# QDRII_mem.net
KiCad netlist of a schematic drawn in Altium Designer
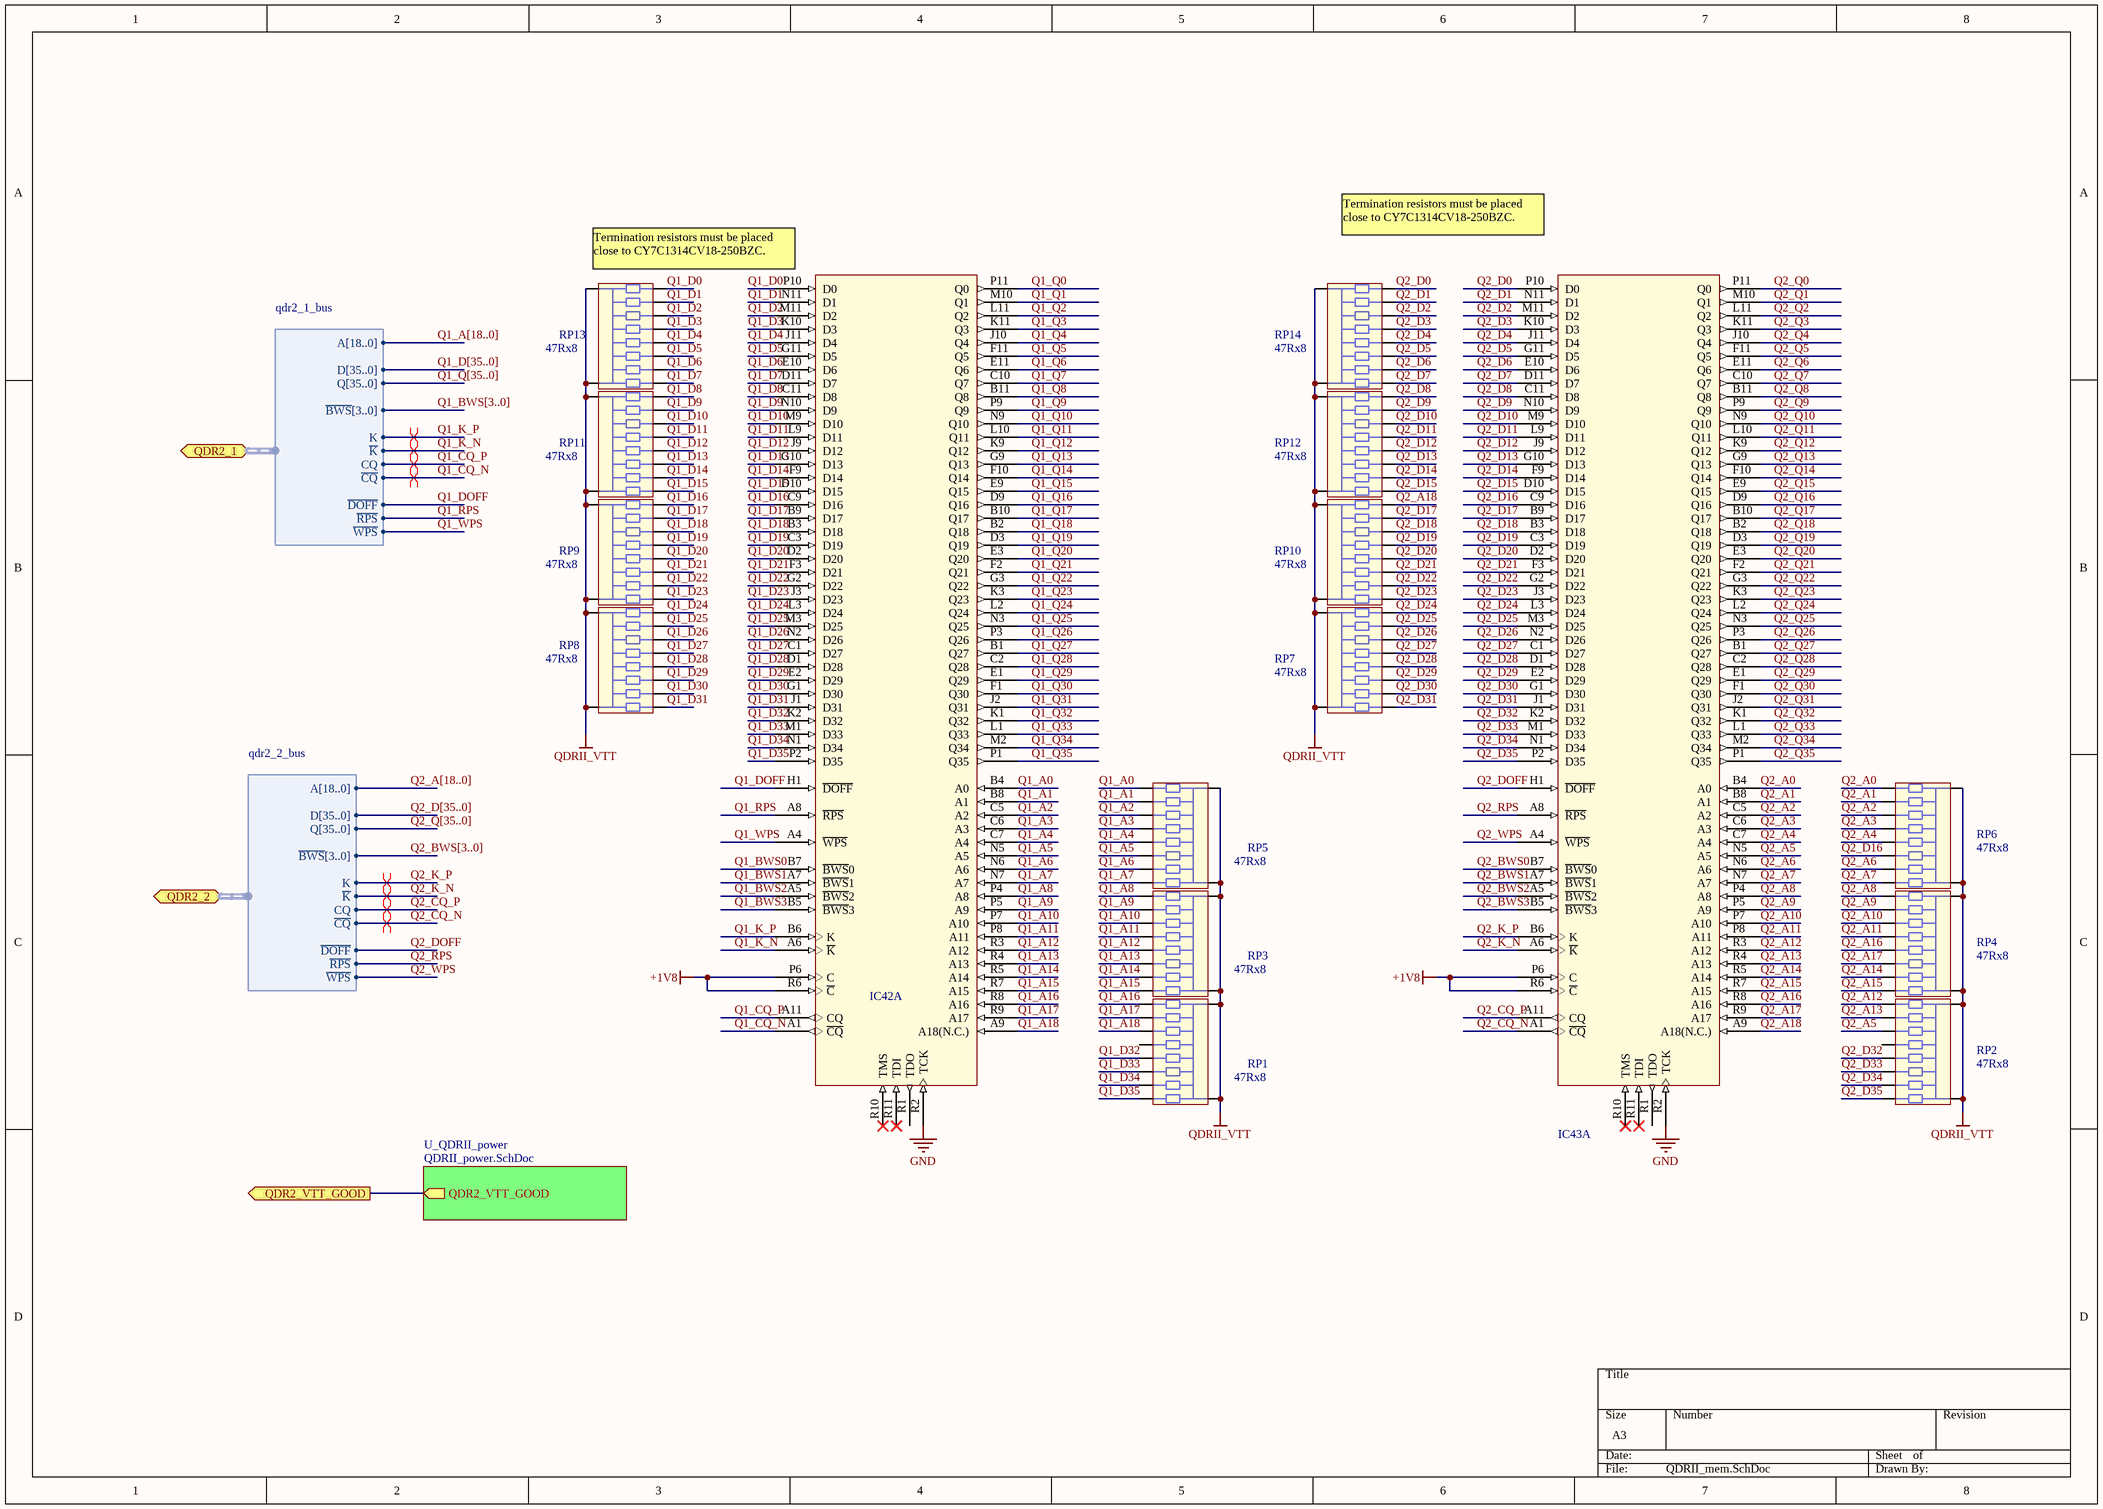
[diagram p0: QDRII_mem.SchDoc]

(export (version "E")
  (design (tool "Eeschema 10.0.6"))
  (components
    (comp (ref "IC42")
      (value "CY7C1314CV18-250BZC")
      (footprint "BGA165C100P11X15_1300X1500X140")
      (description "18-Mbit (512Kx36) QDRII SRAM 2-Word Burst Architecture")
      (libsource (lib "wr_switch") (part "CY7C1314CV18"))
    )
    (comp (ref "IC43")
      (value "CY7C1314CV18-250BZC")
      (footprint "BGA165C100P11X15_1300X1500X140")
      (description "18-Mbit (512Kx36) QDRII SRAM 2-Word Burst Architecture")
      (libsource (lib "wr_switch") (part "CY7C1314CV18"))
    )
    (comp (ref "RP1")
      (value "47Rx8")
      (footprint "EXBE")
      (description "47R, 62.5mW Chip Resistor Bussed Network")
      (fields (field (name "TOLERANCE") "±5%") (field (name "Comment") "47R x 8"))
      (libsource (lib "") (part "EXB-E10C470J_2"))
    )
    (comp (ref "RP2")
      (value "47Rx8")
      (footprint "EXBE")
      (description "47R, 62.5mW Chip Resistor Bussed Network")
      (fields (field (name "TOLERANCE") "±5%") (field (name "Comment") "47R x 8"))
      (libsource (lib "") (part "EXB-E10C470J_5"))
    )
    (comp (ref "RP3")
      (value "47Rx8")
      (footprint "EXBE")
      (description "47R, 62.5mW Chip Resistor Bussed Network")
      (fields (field (name "TOLERANCE") "±5%") (field (name "Comment") "47R x 8"))
      (libsource (lib "") (part "EXB-E10C470J_2"))
    )
    (comp (ref "RP4")
      (value "47Rx8")
      (footprint "EXBE")
      (description "47R, 62.5mW Chip Resistor Bussed Network")
      (fields (field (name "TOLERANCE") "±5%") (field (name "Comment") "47R x 8"))
      (libsource (lib "") (part "EXB-E10C470J_4"))
    )
    (comp (ref "RP5")
      (value "47Rx8")
      (footprint "EXBE")
      (description "47R, 62.5mW Chip Resistor Bussed Network")
      (fields (field (name "TOLERANCE") "±5%") (field (name "Comment") "47R x 8"))
      (libsource (lib "") (part "EXB-E10C470J_2"))
    )
    (comp (ref "RP6")
      (value "47Rx8")
      (footprint "EXBE")
      (description "47R, 62.5mW Chip Resistor Bussed Network")
      (fields (field (name "TOLERANCE") "±5%") (field (name "Comment") "47R x 8"))
      (libsource (lib "") (part "EXB-E10C470J_1"))
    )
    (comp (ref "RP7")
      (value "47Rx8")
      (footprint "EXBE")
      (description "47R, 62.5mW Chip Resistor Bussed Network")
      (fields (field (name "TOLERANCE") "±5%") (field (name "Comment") "47R x 8"))
      (libsource (lib "") (part "EXB-E10C470J_3"))
    )
    (comp (ref "RP8")
      (value "47Rx8")
      (footprint "EXBE")
      (description "47R, 62.5mW Chip Resistor Bussed Network")
      (fields (field (name "TOLERANCE") "±5%") (field (name "Comment") "47R x 8"))
      (libsource (lib "wr_switch") (part "EXB-E10C470J"))
    )
    (comp (ref "RP9")
      (value "47Rx8")
      (footprint "EXBE")
      (description "47R, 62.5mW Chip Resistor Bussed Network")
      (fields (field (name "TOLERANCE") "±5%") (field (name "Comment") "47R x 8"))
      (libsource (lib "wr_switch") (part "EXB-E10C470J"))
    )
    (comp (ref "RP10")
      (value "47Rx8")
      (footprint "EXBE")
      (description "47R, 62.5mW Chip Resistor Bussed Network")
      (fields (field (name "TOLERANCE") "±5%") (field (name "Comment") "47R x 8"))
      (libsource (lib "") (part "EXB-E10C470J_6"))
    )
    (comp (ref "RP11")
      (value "47Rx8")
      (footprint "EXBE")
      (description "47R, 62.5mW Chip Resistor Bussed Network")
      (fields (field (name "TOLERANCE") "±5%") (field (name "Comment") "47R x 8"))
      (libsource (lib "wr_switch") (part "EXB-E10C470J"))
    )
    (comp (ref "RP12")
      (value "47Rx8")
      (footprint "EXBE")
      (description "47R, 62.5mW Chip Resistor Bussed Network")
      (fields (field (name "TOLERANCE") "±5%") (field (name "Comment") "47R x 8"))
      (libsource (lib "wr_switch") (part "EXB-E10C470J"))
    )
    (comp (ref "RP13")
      (value "47Rx8")
      (footprint "EXBE")
      (description "47R, 62.5mW Chip Resistor Bussed Network")
      (fields (field (name "TOLERANCE") "±5%") (field (name "Comment") "47R x 8"))
      (libsource (lib "wr_switch") (part "EXB-E10C470J"))
    )
    (comp (ref "RP14")
      (value "47Rx8")
      (footprint "EXBE")
      (description "47R, 62.5mW Chip Resistor Bussed Network")
      (fields (field (name "TOLERANCE") "±5%") (field (name "Comment") "47R x 8"))
      (libsource (lib "wr_switch") (part "EXB-E10C470J"))
    )
  )
  (nets
    (net (code "3") (name "+1V8") (class "Default")
      (node (ref "IC42") (pin "P6") (pinfunction "C_P6") (pintype "input"))
      (node (ref "IC42") (pin "R6") (pinfunction "~{C}_R6") (pintype "input"))
      (node (ref "IC43") (pin "P6") (pinfunction "C_P6") (pintype "input"))
      (node (ref "IC43") (pin "R6") (pinfunction "~{C}_R6") (pintype "input"))
    )
    (net (code "4") (name "/Q1_A0") (class "Default")
      (node (ref "IC42") (pin "B4") (pinfunction "A0_B4") (pintype "input"))
      (node (ref "RP5") (pin "2") (pinfunction "2_2") (pintype "passive"))
    )
    (net (code "5") (name "/Q1_A1") (class "Default")
      (node (ref "IC42") (pin "B8") (pinfunction "A1_B8") (pintype "input"))
      (node (ref "RP5") (pin "3") (pinfunction "3_3") (pintype "passive"))
    )
    (net (code "6") (name "/Q1_A2") (class "Default")
      (node (ref "IC42") (pin "C5") (pinfunction "A2_C5") (pintype "input"))
      (node (ref "RP5") (pin "4") (pinfunction "4_4") (pintype "passive"))
    )
    (net (code "7") (name "/Q1_A3") (class "Default")
      (node (ref "IC42") (pin "C6") (pinfunction "A3_C6") (pintype "input"))
      (node (ref "RP5") (pin "5") (pinfunction "5_5") (pintype "passive"))
    )
    (net (code "8") (name "/Q1_A4") (class "Default")
      (node (ref "IC42") (pin "C7") (pinfunction "A4_C7") (pintype "input"))
      (node (ref "RP5") (pin "7") (pinfunction "7_7") (pintype "passive"))
    )
    (net (code "9") (name "/Q1_A5") (class "Default")
      (node (ref "IC42") (pin "N5") (pinfunction "A5_N5") (pintype "input"))
      (node (ref "RP5") (pin "8") (pinfunction "8_8") (pintype "passive"))
    )
    (net (code "10") (name "/Q1_A6") (class "Default")
      (node (ref "IC42") (pin "N6") (pinfunction "A6_N6") (pintype "input"))
      (node (ref "RP5") (pin "9") (pinfunction "9_9") (pintype "passive"))
    )
    (net (code "11") (name "/Q1_A7") (class "Default")
      (node (ref "IC42") (pin "N7") (pinfunction "A7_N7") (pintype "input"))
      (node (ref "RP5") (pin "10") (pinfunction "10_10") (pintype "passive"))
    )
    (net (code "12") (name "/Q1_A8") (class "Default")
      (node (ref "IC42") (pin "P4") (pinfunction "A8_P4") (pintype "input"))
      (node (ref "RP3") (pin "2") (pinfunction "2_2") (pintype "passive"))
    )
    (net (code "13") (name "/Q1_A9") (class "Default")
      (node (ref "IC42") (pin "P5") (pinfunction "A9_P5") (pintype "input"))
      (node (ref "RP3") (pin "3") (pinfunction "3_3") (pintype "passive"))
    )
    (net (code "14") (name "/Q1_A10") (class "Default")
      (node (ref "IC42") (pin "P7") (pinfunction "A10_P7") (pintype "input"))
      (node (ref "RP3") (pin "4") (pinfunction "4_4") (pintype "passive"))
    )
    (net (code "15") (name "/Q1_A11") (class "Default")
      (node (ref "IC42") (pin "P8") (pinfunction "A11_P8") (pintype "input"))
      (node (ref "RP3") (pin "5") (pinfunction "5_5") (pintype "passive"))
    )
    (net (code "16") (name "/Q1_A12") (class "Default")
      (node (ref "IC42") (pin "R3") (pinfunction "A12_R3") (pintype "input"))
      (node (ref "RP3") (pin "7") (pinfunction "7_7") (pintype "passive"))
    )
    (net (code "17") (name "/Q1_A13") (class "Default")
      (node (ref "IC42") (pin "R4") (pinfunction "A13_R4") (pintype "input"))
      (node (ref "RP3") (pin "8") (pinfunction "8_8") (pintype "passive"))
    )
    (net (code "18") (name "/Q1_A14") (class "Default")
      (node (ref "IC42") (pin "R5") (pinfunction "A14_R5") (pintype "input"))
      (node (ref "RP3") (pin "9") (pinfunction "9_9") (pintype "passive"))
    )
    (net (code "19") (name "/Q1_A15") (class "Default")
      (node (ref "IC42") (pin "R7") (pinfunction "A15_R7") (pintype "input"))
      (node (ref "RP3") (pin "10") (pinfunction "10_10") (pintype "passive"))
    )
    (net (code "20") (name "/Q1_A16") (class "Default")
      (node (ref "IC42") (pin "R8") (pinfunction "A16_R8") (pintype "input"))
      (node (ref "RP1") (pin "2") (pinfunction "2_2") (pintype "passive"))
    )
    (net (code "21") (name "/Q1_A17") (class "Default")
      (node (ref "IC42") (pin "R9") (pinfunction "A17_R9") (pintype "input"))
      (node (ref "RP1") (pin "3") (pinfunction "3_3") (pintype "passive"))
    )
    (net (code "22") (name "/Q1_A18") (class "Default")
      (node (ref "IC42") (pin "A9") (pinfunction "A18(N.C.)_A9") (pintype "input"))
      (node (ref "RP1") (pin "4") (pinfunction "4_4") (pintype "passive"))
    )
    (net (code "23") (name "/Q1_BWS0") (class "Default")
      (node (ref "IC42") (pin "B7") (pinfunction "~{BWS}0_B7") (pintype "input"))
    )
    (net (code "24") (name "/Q1_BWS1") (class "Default")
      (node (ref "IC42") (pin "A7") (pinfunction "~{BWS}1_A7") (pintype "input"))
    )
    (net (code "25") (name "/Q1_BWS2") (class "Default")
      (node (ref "IC42") (pin "A5") (pinfunction "~{BWS}2_A5") (pintype "input"))
    )
    (net (code "26") (name "/Q1_BWS3") (class "Default")
      (node (ref "IC42") (pin "B5") (pinfunction "~{BWS}3_B5") (pintype "input"))
    )
    (net (code "28") (name "/Q1_CQ_N") (class "Default")
      (node (ref "IC42") (pin "A1") (pinfunction "~{CQ}_A1") (pintype "output"))
    )
    (net (code "29") (name "/Q1_CQ_P") (class "Default")
      (node (ref "IC42") (pin "A11") (pinfunction "CQ_A11") (pintype "output"))
    )
    (net (code "30") (name "/Q1_D0") (class "Default")
      (node (ref "IC42") (pin "P10") (pinfunction "D0_P10") (pintype "input"))
      (node (ref "RP13") (pin "10") (pinfunction "10_10") (pintype "passive"))
    )
    (net (code "31") (name "/Q1_D1") (class "Default")
      (node (ref "IC42") (pin "N11") (pinfunction "D1_N11") (pintype "input"))
      (node (ref "RP13") (pin "9") (pinfunction "9_9") (pintype "passive"))
    )
    (net (code "32") (name "/Q1_D2") (class "Default")
      (node (ref "IC42") (pin "M11") (pinfunction "D2_M11") (pintype "input"))
      (node (ref "RP13") (pin "8") (pinfunction "8_8") (pintype "passive"))
    )
    (net (code "33") (name "/Q1_D3") (class "Default")
      (node (ref "IC42") (pin "K10") (pinfunction "D3_K10") (pintype "input"))
      (node (ref "RP13") (pin "7") (pinfunction "7_7") (pintype "passive"))
    )
    (net (code "34") (name "/Q1_D4") (class "Default")
      (node (ref "IC42") (pin "J11") (pinfunction "D4_J11") (pintype "input"))
      (node (ref "RP13") (pin "5") (pinfunction "5_5") (pintype "passive"))
    )
    (net (code "35") (name "/Q1_D5") (class "Default")
      (node (ref "IC42") (pin "G11") (pinfunction "D5_G11") (pintype "input"))
      (node (ref "RP13") (pin "4") (pinfunction "4_4") (pintype "passive"))
    )
    (net (code "36") (name "/Q1_D6") (class "Default")
      (node (ref "IC42") (pin "E10") (pinfunction "D6_E10") (pintype "input"))
      (node (ref "RP13") (pin "3") (pinfunction "3_3") (pintype "passive"))
    )
    (net (code "37") (name "/Q1_D7") (class "Default")
      (node (ref "IC42") (pin "D11") (pinfunction "D7_D11") (pintype "input"))
      (node (ref "RP13") (pin "2") (pinfunction "2_2") (pintype "passive"))
    )
    (net (code "38") (name "/Q1_D8") (class "Default")
      (node (ref "IC42") (pin "C11") (pinfunction "D8_C11") (pintype "input"))
      (node (ref "RP11") (pin "10") (pinfunction "10_10") (pintype "passive"))
    )
    (net (code "39") (name "/Q1_D9") (class "Default")
      (node (ref "IC42") (pin "N10") (pinfunction "D9_N10") (pintype "input"))
      (node (ref "RP11") (pin "9") (pinfunction "9_9") (pintype "passive"))
    )
    (net (code "40") (name "/Q1_D10") (class "Default")
      (node (ref "IC42") (pin "M9") (pinfunction "D10_M9") (pintype "input"))
      (node (ref "RP11") (pin "8") (pinfunction "8_8") (pintype "passive"))
    )
    (net (code "41") (name "/Q1_D11") (class "Default")
      (node (ref "IC42") (pin "L9") (pinfunction "D11_L9") (pintype "input"))
      (node (ref "RP11") (pin "7") (pinfunction "7_7") (pintype "passive"))
    )
    (net (code "42") (name "/Q1_D12") (class "Default")
      (node (ref "IC42") (pin "J9") (pinfunction "D12_J9") (pintype "input"))
      (node (ref "RP11") (pin "5") (pinfunction "5_5") (pintype "passive"))
    )
    (net (code "43") (name "/Q1_D13") (class "Default")
      (node (ref "IC42") (pin "G10") (pinfunction "D13_G10") (pintype "input"))
      (node (ref "RP11") (pin "4") (pinfunction "4_4") (pintype "passive"))
    )
    (net (code "44") (name "/Q1_D14") (class "Default")
      (node (ref "IC42") (pin "F9") (pinfunction "D14_F9") (pintype "input"))
      (node (ref "RP11") (pin "3") (pinfunction "3_3") (pintype "passive"))
    )
    (net (code "45") (name "/Q1_D15") (class "Default")
      (node (ref "IC42") (pin "D10") (pinfunction "D15_D10") (pintype "input"))
      (node (ref "RP11") (pin "2") (pinfunction "2_2") (pintype "passive"))
    )
    (net (code "46") (name "/Q1_D16") (class "Default")
      (node (ref "IC42") (pin "C9") (pinfunction "D16_C9") (pintype "input"))
      (node (ref "RP9") (pin "10") (pinfunction "10_10") (pintype "passive"))
    )
    (net (code "47") (name "/Q1_D17") (class "Default")
      (node (ref "IC42") (pin "B9") (pinfunction "D17_B9") (pintype "input"))
      (node (ref "RP9") (pin "9") (pinfunction "9_9") (pintype "passive"))
    )
    (net (code "48") (name "/Q1_D18") (class "Default")
      (node (ref "IC42") (pin "B3") (pinfunction "D18_B3") (pintype "input"))
      (node (ref "RP9") (pin "8") (pinfunction "8_8") (pintype "passive"))
    )
    (net (code "49") (name "/Q1_D19") (class "Default")
      (node (ref "IC42") (pin "C3") (pinfunction "D19_C3") (pintype "input"))
      (node (ref "RP9") (pin "7") (pinfunction "7_7") (pintype "passive"))
    )
    (net (code "50") (name "/Q1_D20") (class "Default")
      (node (ref "IC42") (pin "D2") (pinfunction "D20_D2") (pintype "input"))
      (node (ref "RP9") (pin "5") (pinfunction "5_5") (pintype "passive"))
    )
    (net (code "51") (name "/Q1_D21") (class "Default")
      (node (ref "IC42") (pin "F3") (pinfunction "D21_F3") (pintype "input"))
      (node (ref "RP9") (pin "4") (pinfunction "4_4") (pintype "passive"))
    )
    (net (code "52") (name "/Q1_D22") (class "Default")
      (node (ref "IC42") (pin "G2") (pinfunction "D22_G2") (pintype "input"))
      (node (ref "RP9") (pin "3") (pinfunction "3_3") (pintype "passive"))
    )
    (net (code "53") (name "/Q1_D23") (class "Default")
      (node (ref "IC42") (pin "J3") (pinfunction "D23_J3") (pintype "input"))
      (node (ref "RP9") (pin "2") (pinfunction "2_2") (pintype "passive"))
    )
    (net (code "54") (name "/Q1_D24") (class "Default")
      (node (ref "IC42") (pin "L3") (pinfunction "D24_L3") (pintype "input"))
      (node (ref "RP8") (pin "10") (pinfunction "10_10") (pintype "passive"))
    )
    (net (code "55") (name "/Q1_D25") (class "Default")
      (node (ref "IC42") (pin "M3") (pinfunction "D25_M3") (pintype "input"))
      (node (ref "RP8") (pin "9") (pinfunction "9_9") (pintype "passive"))
    )
    (net (code "56") (name "/Q1_D26") (class "Default")
      (node (ref "IC42") (pin "N2") (pinfunction "D26_N2") (pintype "input"))
      (node (ref "RP8") (pin "8") (pinfunction "8_8") (pintype "passive"))
    )
    (net (code "57") (name "/Q1_D27") (class "Default")
      (node (ref "IC42") (pin "C1") (pinfunction "D27_C1") (pintype "input"))
      (node (ref "RP8") (pin "7") (pinfunction "7_7") (pintype "passive"))
    )
    (net (code "58") (name "/Q1_D28") (class "Default")
      (node (ref "IC42") (pin "D1") (pinfunction "D28_D1") (pintype "input"))
      (node (ref "RP8") (pin "5") (pinfunction "5_5") (pintype "passive"))
    )
    (net (code "59") (name "/Q1_D29") (class "Default")
      (node (ref "IC42") (pin "E2") (pinfunction "D29_E2") (pintype "input"))
      (node (ref "RP8") (pin "4") (pinfunction "4_4") (pintype "passive"))
    )
    (net (code "60") (name "/Q1_D30") (class "Default")
      (node (ref "IC42") (pin "G1") (pinfunction "D30_G1") (pintype "input"))
      (node (ref "RP8") (pin "3") (pinfunction "3_3") (pintype "passive"))
    )
    (net (code "61") (name "/Q1_D31") (class "Default")
      (node (ref "IC42") (pin "J1") (pinfunction "D31_J1") (pintype "input"))
      (node (ref "RP8") (pin "2") (pinfunction "2_2") (pintype "passive"))
    )
    (net (code "62") (name "/Q1_D32") (class "Default")
      (node (ref "IC42") (pin "K2") (pinfunction "D32_K2") (pintype "input"))
      (node (ref "RP1") (pin "7") (pinfunction "7_7") (pintype "passive"))
    )
    (net (code "63") (name "/Q1_D33") (class "Default")
      (node (ref "IC42") (pin "M1") (pinfunction "D33_M1") (pintype "input"))
      (node (ref "RP1") (pin "8") (pinfunction "8_8") (pintype "passive"))
    )
    (net (code "64") (name "/Q1_D34") (class "Default")
      (node (ref "IC42") (pin "N1") (pinfunction "D34_N1") (pintype "input"))
      (node (ref "RP1") (pin "9") (pinfunction "9_9") (pintype "passive"))
    )
    (net (code "65") (name "/Q1_D35") (class "Default")
      (node (ref "IC42") (pin "P2") (pinfunction "D35_P2") (pintype "input"))
      (node (ref "RP1") (pin "10") (pinfunction "10_10") (pintype "passive"))
    )
    (net (code "66") (name "/Q1_DOFF") (class "Default")
      (node (ref "IC42") (pin "H1") (pinfunction "~{DOFF}_H1") (pintype "input"))
    )
    (net (code "68") (name "/Q1_K_N") (class "Default")
      (node (ref "IC42") (pin "A6") (pinfunction "~{K}_A6") (pintype "input"))
    )
    (net (code "69") (name "/Q1_K_P") (class "Default")
      (node (ref "IC42") (pin "B6") (pinfunction "K_B6") (pintype "input"))
    )
    (net (code "70") (name "/Q1_Q0") (class "Default")
      (node (ref "IC42") (pin "P11") (pinfunction "Q0_P11") (pintype "output"))
    )
    (net (code "71") (name "/Q1_Q1") (class "Default")
      (node (ref "IC42") (pin "M10") (pinfunction "Q1_M10") (pintype "output"))
    )
    (net (code "72") (name "/Q1_Q2") (class "Default")
      (node (ref "IC42") (pin "L11") (pinfunction "Q2_L11") (pintype "output"))
    )
    (net (code "73") (name "/Q1_Q3") (class "Default")
      (node (ref "IC42") (pin "K11") (pinfunction "Q3_K11") (pintype "output"))
    )
    (net (code "74") (name "/Q1_Q4") (class "Default")
      (node (ref "IC42") (pin "J10") (pinfunction "Q4_J10") (pintype "output"))
    )
    (net (code "75") (name "/Q1_Q5") (class "Default")
      (node (ref "IC42") (pin "F11") (pinfunction "Q5_F11") (pintype "output"))
    )
    (net (code "76") (name "/Q1_Q6") (class "Default")
      (node (ref "IC42") (pin "E11") (pinfunction "Q6_E11") (pintype "output"))
    )
    (net (code "77") (name "/Q1_Q7") (class "Default")
      (node (ref "IC42") (pin "C10") (pinfunction "Q7_C10") (pintype "output"))
    )
    (net (code "78") (name "/Q1_Q8") (class "Default")
      (node (ref "IC42") (pin "B11") (pinfunction "Q8_B11") (pintype "output"))
    )
    (net (code "79") (name "/Q1_Q9") (class "Default")
      (node (ref "IC42") (pin "P9") (pinfunction "Q9_P9") (pintype "output"))
    )
    (net (code "80") (name "/Q1_Q10") (class "Default")
      (node (ref "IC42") (pin "N9") (pinfunction "Q10_N9") (pintype "output"))
    )
    (net (code "81") (name "/Q1_Q11") (class "Default")
      (node (ref "IC42") (pin "L10") (pinfunction "Q11_L10") (pintype "output"))
    )
    (net (code "82") (name "/Q1_Q12") (class "Default")
      (node (ref "IC42") (pin "K9") (pinfunction "Q12_K9") (pintype "output"))
    )
    (net (code "83") (name "/Q1_Q13") (class "Default")
      (node (ref "IC42") (pin "G9") (pinfunction "Q13_G9") (pintype "output"))
    )
    (net (code "84") (name "/Q1_Q14") (class "Default")
      (node (ref "IC42") (pin "F10") (pinfunction "Q14_F10") (pintype "output"))
    )
    (net (code "85") (name "/Q1_Q15") (class "Default")
      (node (ref "IC42") (pin "E9") (pinfunction "Q15_E9") (pintype "output"))
    )
    (net (code "86") (name "/Q1_Q16") (class "Default")
      (node (ref "IC42") (pin "D9") (pinfunction "Q16_D9") (pintype "output"))
    )
    (net (code "87") (name "/Q1_Q17") (class "Default")
      (node (ref "IC42") (pin "B10") (pinfunction "Q17_B10") (pintype "output"))
    )
    (net (code "88") (name "/Q1_Q18") (class "Default")
      (node (ref "IC42") (pin "B2") (pinfunction "Q18_B2") (pintype "output"))
    )
    (net (code "89") (name "/Q1_Q19") (class "Default")
      (node (ref "IC42") (pin "D3") (pinfunction "Q19_D3") (pintype "output"))
    )
    (net (code "90") (name "/Q1_Q20") (class "Default")
      (node (ref "IC42") (pin "E3") (pinfunction "Q20_E3") (pintype "output"))
    )
    (net (code "91") (name "/Q1_Q21") (class "Default")
      (node (ref "IC42") (pin "F2") (pinfunction "Q21_F2") (pintype "output"))
    )
    (net (code "92") (name "/Q1_Q22") (class "Default")
      (node (ref "IC42") (pin "G3") (pinfunction "Q22_G3") (pintype "output"))
    )
    (net (code "93") (name "/Q1_Q23") (class "Default")
      (node (ref "IC42") (pin "K3") (pinfunction "Q23_K3") (pintype "output"))
    )
    (net (code "94") (name "/Q1_Q24") (class "Default")
      (node (ref "IC42") (pin "L2") (pinfunction "Q24_L2") (pintype "output"))
    )
    (net (code "95") (name "/Q1_Q25") (class "Default")
      (node (ref "IC42") (pin "N3") (pinfunction "Q25_N3") (pintype "output"))
    )
    (net (code "96") (name "/Q1_Q26") (class "Default")
      (node (ref "IC42") (pin "P3") (pinfunction "Q26_P3") (pintype "output"))
    )
    (net (code "97") (name "/Q1_Q27") (class "Default")
      (node (ref "IC42") (pin "B1") (pinfunction "Q27_B1") (pintype "output"))
    )
    (net (code "98") (name "/Q1_Q28") (class "Default")
      (node (ref "IC42") (pin "C2") (pinfunction "Q28_C2") (pintype "output"))
    )
    (net (code "99") (name "/Q1_Q29") (class "Default")
      (node (ref "IC42") (pin "E1") (pinfunction "Q29_E1") (pintype "output"))
    )
    (net (code "100") (name "/Q1_Q30") (class "Default")
      (node (ref "IC42") (pin "F1") (pinfunction "Q30_F1") (pintype "output"))
    )
    (net (code "101") (name "/Q1_Q31") (class "Default")
      (node (ref "IC42") (pin "J2") (pinfunction "Q31_J2") (pintype "output"))
    )
    (net (code "102") (name "/Q1_Q32") (class "Default")
      (node (ref "IC42") (pin "K1") (pinfunction "Q32_K1") (pintype "output"))
    )
    (net (code "103") (name "/Q1_Q33") (class "Default")
      (node (ref "IC42") (pin "L1") (pinfunction "Q33_L1") (pintype "output"))
    )
    (net (code "104") (name "/Q1_Q34") (class "Default")
      (node (ref "IC42") (pin "M2") (pinfunction "Q34_M2") (pintype "output"))
    )
    (net (code "105") (name "/Q1_Q35") (class "Default")
      (node (ref "IC42") (pin "P1") (pinfunction "Q35_P1") (pintype "output"))
    )
    (net (code "107") (name "/Q1_RPS") (class "Default")
      (node (ref "IC42") (pin "A8") (pinfunction "~{RPS}_A8") (pintype "input"))
    )
    (net (code "108") (name "/Q1_WPS") (class "Default")
      (node (ref "IC42") (pin "A4") (pinfunction "~{WPS}_A4") (pintype "input"))
    )
    (net (code "109") (name "/Q2_A0") (class "Default")
      (node (ref "IC43") (pin "B4") (pinfunction "A0_B4") (pintype "input"))
      (node (ref "RP6") (pin "5") (pinfunction "5_5") (pintype "passive"))
    )
    (net (code "110") (name "/Q2_A1") (class "Default")
      (node (ref "IC43") (pin "B8") (pinfunction "A1_B8") (pintype "input"))
      (node (ref "RP6") (pin "10") (pinfunction "10_10") (pintype "passive"))
    )
    (net (code "111") (name "/Q2_A2") (class "Default")
      (node (ref "IC43") (pin "C5") (pinfunction "A2_C5") (pintype "input"))
      (node (ref "RP6") (pin "7") (pinfunction "7_7") (pintype "passive"))
    )
    (net (code "112") (name "/Q2_A3") (class "Default")
      (node (ref "IC43") (pin "C6") (pinfunction "A3_C6") (pintype "input"))
      (node (ref "RP6") (pin "8") (pinfunction "8_8") (pintype "passive"))
    )
    (net (code "113") (name "/Q2_A4") (class "Default")
      (node (ref "IC43") (pin "C7") (pinfunction "A4_C7") (pintype "input"))
      (node (ref "RP6") (pin "9") (pinfunction "9_9") (pintype "passive"))
    )
    (net (code "114") (name "/Q2_A5") (class "Default")
      (node (ref "IC43") (pin "N5") (pinfunction "A5_N5") (pintype "input"))
      (node (ref "RP2") (pin "9") (pinfunction "9_9") (pintype "passive"))
    )
    (net (code "115") (name "/Q2_A6") (class "Default")
      (node (ref "IC43") (pin "N6") (pinfunction "A6_N6") (pintype "input"))
      (node (ref "RP6") (pin "3") (pinfunction "3_3") (pintype "passive"))
    )
    (net (code "116") (name "/Q2_A7") (class "Default")
      (node (ref "IC43") (pin "N7") (pinfunction "A7_N7") (pintype "input"))
      (node (ref "RP6") (pin "4") (pinfunction "4_4") (pintype "passive"))
    )
    (net (code "117") (name "/Q2_A8") (class "Default")
      (node (ref "IC43") (pin "P4") (pinfunction "A8_P4") (pintype "input"))
      (node (ref "RP4") (pin "10") (pinfunction "10_10") (pintype "passive"))
    )
    (net (code "118") (name "/Q2_A9") (class "Default")
      (node (ref "IC43") (pin "P5") (pinfunction "A9_P5") (pintype "input"))
      (node (ref "RP4") (pin "9") (pinfunction "9_9") (pintype "passive"))
    )
    (net (code "119") (name "/Q2_A10") (class "Default")
      (node (ref "IC43") (pin "P7") (pinfunction "A10_P7") (pintype "input"))
      (node (ref "RP4") (pin "5") (pinfunction "5_5") (pintype "passive"))
    )
    (net (code "120") (name "/Q2_A11") (class "Default")
      (node (ref "IC43") (pin "P8") (pinfunction "A11_P8") (pintype "input"))
      (node (ref "RP4") (pin "3") (pinfunction "3_3") (pintype "passive"))
    )
    (net (code "121") (name "/Q2_A12") (class "Default")
      (node (ref "IC43") (pin "R3") (pinfunction "A12_R3") (pintype "input"))
      (node (ref "RP2") (pin "10") (pinfunction "10_10") (pintype "passive"))
    )
    (net (code "122") (name "/Q2_A13") (class "Default")
      (node (ref "IC43") (pin "R4") (pinfunction "A13_R4") (pintype "input"))
      (node (ref "RP2") (pin "7") (pinfunction "7_7") (pintype "passive"))
    )
    (net (code "123") (name "/Q2_A14") (class "Default")
      (node (ref "IC43") (pin "R5") (pinfunction "A14_R5") (pintype "input"))
      (node (ref "RP4") (pin "8") (pinfunction "8_8") (pintype "passive"))
    )
    (net (code "124") (name "/Q2_A15") (class "Default")
      (node (ref "IC43") (pin "R7") (pinfunction "A15_R7") (pintype "input"))
      (node (ref "RP4") (pin "7") (pinfunction "7_7") (pintype "passive"))
    )
    (net (code "125") (name "/Q2_A16") (class "Default")
      (node (ref "IC43") (pin "R8") (pinfunction "A16_R8") (pintype "input"))
      (node (ref "RP4") (pin "4") (pinfunction "4_4") (pintype "passive"))
    )
    (net (code "126") (name "/Q2_A17") (class "Default")
      (node (ref "IC43") (pin "R9") (pinfunction "A17_R9") (pintype "input"))
      (node (ref "RP4") (pin "2") (pinfunction "2_2") (pintype "passive"))
    )
    (net (code "127") (name "/Q2_A18") (class "Default")
      (node (ref "IC43") (pin "A9") (pinfunction "A18(N.C.)_A9") (pintype "input"))
      (node (ref "RP10") (pin "5") (pinfunction "5_5") (pintype "passive"))
    )
    (net (code "128") (name "/Q2_BWS0") (class "Default")
      (node (ref "IC43") (pin "B7") (pinfunction "~{BWS}0_B7") (pintype "input"))
    )
    (net (code "129") (name "/Q2_BWS1") (class "Default")
      (node (ref "IC43") (pin "A7") (pinfunction "~{BWS}1_A7") (pintype "input"))
    )
    (net (code "130") (name "/Q2_BWS2") (class "Default")
      (node (ref "IC43") (pin "A5") (pinfunction "~{BWS}2_A5") (pintype "input"))
    )
    (net (code "131") (name "/Q2_BWS3") (class "Default")
      (node (ref "IC43") (pin "B5") (pinfunction "~{BWS}3_B5") (pintype "input"))
    )
    (net (code "133") (name "/Q2_CQ_N") (class "Default")
      (node (ref "IC43") (pin "A1") (pinfunction "~{CQ}_A1") (pintype "output"))
    )
    (net (code "134") (name "/Q2_CQ_P") (class "Default")
      (node (ref "IC43") (pin "A11") (pinfunction "CQ_A11") (pintype "output"))
    )
    (net (code "135") (name "/Q2_D0") (class "Default")
      (node (ref "IC43") (pin "P10") (pinfunction "D0_P10") (pintype "input"))
      (node (ref "RP14") (pin "10") (pinfunction "10_10") (pintype "passive"))
    )
    (net (code "136") (name "/Q2_D1") (class "Default")
      (node (ref "IC43") (pin "N11") (pinfunction "D1_N11") (pintype "input"))
      (node (ref "RP14") (pin "9") (pinfunction "9_9") (pintype "passive"))
    )
    (net (code "137") (name "/Q2_D2") (class "Default")
      (node (ref "IC43") (pin "M11") (pinfunction "D2_M11") (pintype "input"))
      (node (ref "RP14") (pin "8") (pinfunction "8_8") (pintype "passive"))
    )
    (net (code "138") (name "/Q2_D3") (class "Default")
      (node (ref "IC43") (pin "K10") (pinfunction "D3_K10") (pintype "input"))
      (node (ref "RP14") (pin "7") (pinfunction "7_7") (pintype "passive"))
    )
    (net (code "139") (name "/Q2_D4") (class "Default")
      (node (ref "IC43") (pin "J11") (pinfunction "D4_J11") (pintype "input"))
      (node (ref "RP14") (pin "5") (pinfunction "5_5") (pintype "passive"))
    )
    (net (code "140") (name "/Q2_D5") (class "Default")
      (node (ref "IC43") (pin "G11") (pinfunction "D5_G11") (pintype "input"))
      (node (ref "RP14") (pin "4") (pinfunction "4_4") (pintype "passive"))
    )
    (net (code "141") (name "/Q2_D6") (class "Default")
      (node (ref "IC43") (pin "E10") (pinfunction "D6_E10") (pintype "input"))
      (node (ref "RP14") (pin "3") (pinfunction "3_3") (pintype "passive"))
    )
    (net (code "142") (name "/Q2_D7") (class "Default")
      (node (ref "IC43") (pin "D11") (pinfunction "D7_D11") (pintype "input"))
      (node (ref "RP14") (pin "2") (pinfunction "2_2") (pintype "passive"))
    )
    (net (code "143") (name "/Q2_D8") (class "Default")
      (node (ref "IC43") (pin "C11") (pinfunction "D8_C11") (pintype "input"))
      (node (ref "RP12") (pin "10") (pinfunction "10_10") (pintype "passive"))
    )
    (net (code "144") (name "/Q2_D9") (class "Default")
      (node (ref "IC43") (pin "N10") (pinfunction "D9_N10") (pintype "input"))
      (node (ref "RP12") (pin "9") (pinfunction "9_9") (pintype "passive"))
    )
    (net (code "145") (name "/Q2_D10") (class "Default")
      (node (ref "IC43") (pin "M9") (pinfunction "D10_M9") (pintype "input"))
      (node (ref "RP12") (pin "8") (pinfunction "8_8") (pintype "passive"))
    )
    (net (code "146") (name "/Q2_D11") (class "Default")
      (node (ref "IC43") (pin "L9") (pinfunction "D11_L9") (pintype "input"))
      (node (ref "RP12") (pin "7") (pinfunction "7_7") (pintype "passive"))
    )
    (net (code "147") (name "/Q2_D12") (class "Default")
      (node (ref "IC43") (pin "J9") (pinfunction "D12_J9") (pintype "input"))
      (node (ref "RP12") (pin "5") (pinfunction "5_5") (pintype "passive"))
    )
    (net (code "148") (name "/Q2_D13") (class "Default")
      (node (ref "IC43") (pin "G10") (pinfunction "D13_G10") (pintype "input"))
      (node (ref "RP12") (pin "4") (pinfunction "4_4") (pintype "passive"))
    )
    (net (code "149") (name "/Q2_D14") (class "Default")
      (node (ref "IC43") (pin "F9") (pinfunction "D14_F9") (pintype "input"))
      (node (ref "RP12") (pin "3") (pinfunction "3_3") (pintype "passive"))
    )
    (net (code "150") (name "/Q2_D15") (class "Default")
      (node (ref "IC43") (pin "D10") (pinfunction "D15_D10") (pintype "input"))
      (node (ref "RP12") (pin "2") (pinfunction "2_2") (pintype "passive"))
    )
    (net (code "151") (name "/Q2_D16") (class "Default")
      (node (ref "IC43") (pin "C9") (pinfunction "D16_C9") (pintype "input"))
      (node (ref "RP6") (pin "2") (pinfunction "2_2") (pintype "passive"))
    )
    (net (code "152") (name "/Q2_D17") (class "Default")
      (node (ref "IC43") (pin "B9") (pinfunction "D17_B9") (pintype "input"))
      (node (ref "RP10") (pin "4") (pinfunction "4_4") (pintype "passive"))
    )
    (net (code "153") (name "/Q2_D18") (class "Default")
      (node (ref "IC43") (pin "B3") (pinfunction "D18_B3") (pintype "input"))
      (node (ref "RP10") (pin "10") (pinfunction "10_10") (pintype "passive"))
    )
    (net (code "154") (name "/Q2_D19") (class "Default")
      (node (ref "IC43") (pin "C3") (pinfunction "D19_C3") (pintype "input"))
      (node (ref "RP10") (pin "9") (pinfunction "9_9") (pintype "passive"))
    )
    (net (code "155") (name "/Q2_D20") (class "Default")
      (node (ref "IC43") (pin "D2") (pinfunction "D20_D2") (pintype "input"))
      (node (ref "RP10") (pin "8") (pinfunction "8_8") (pintype "passive"))
    )
    (net (code "156") (name "/Q2_D21") (class "Default")
      (node (ref "IC43") (pin "F3") (pinfunction "D21_F3") (pintype "input"))
      (node (ref "RP10") (pin "2") (pinfunction "2_2") (pintype "passive"))
    )
    (net (code "157") (name "/Q2_D22") (class "Default")
      (node (ref "IC43") (pin "G2") (pinfunction "D22_G2") (pintype "input"))
      (node (ref "RP10") (pin "7") (pinfunction "7_7") (pintype "passive"))
    )
    (net (code "158") (name "/Q2_D23") (class "Default")
      (node (ref "IC43") (pin "J3") (pinfunction "D23_J3") (pintype "input"))
      (node (ref "RP10") (pin "3") (pinfunction "3_3") (pintype "passive"))
    )
    (net (code "159") (name "/Q2_D24") (class "Default")
      (node (ref "IC43") (pin "L3") (pinfunction "D24_L3") (pintype "input"))
      (node (ref "RP7") (pin "4") (pinfunction "4_4") (pintype "passive"))
    )
    (net (code "160") (name "/Q2_D25") (class "Default")
      (node (ref "IC43") (pin "M3") (pinfunction "D25_M3") (pintype "input"))
      (node (ref "RP7") (pin "3") (pinfunction "3_3") (pintype "passive"))
    )
    (net (code "161") (name "/Q2_D26") (class "Default")
      (node (ref "IC43") (pin "N2") (pinfunction "D26_N2") (pintype "input"))
      (node (ref "RP7") (pin "2") (pinfunction "2_2") (pintype "passive"))
    )
    (net (code "162") (name "/Q2_D27") (class "Default")
      (node (ref "IC43") (pin "C1") (pinfunction "D27_C1") (pintype "input"))
      (node (ref "RP7") (pin "10") (pinfunction "10_10") (pintype "passive"))
    )
    (net (code "163") (name "/Q2_D28") (class "Default")
      (node (ref "IC43") (pin "D1") (pinfunction "D28_D1") (pintype "input"))
      (node (ref "RP7") (pin "9") (pinfunction "9_9") (pintype "passive"))
    )
    (net (code "164") (name "/Q2_D29") (class "Default")
      (node (ref "IC43") (pin "E2") (pinfunction "D29_E2") (pintype "input"))
      (node (ref "RP7") (pin "8") (pinfunction "8_8") (pintype "passive"))
    )
    (net (code "165") (name "/Q2_D30") (class "Default")
      (node (ref "IC43") (pin "G1") (pinfunction "D30_G1") (pintype "input"))
      (node (ref "RP7") (pin "7") (pinfunction "7_7") (pintype "passive"))
    )
    (net (code "166") (name "/Q2_D31") (class "Default")
      (node (ref "IC43") (pin "J1") (pinfunction "D31_J1") (pintype "input"))
      (node (ref "RP7") (pin "5") (pinfunction "5_5") (pintype "passive"))
    )
    (net (code "167") (name "/Q2_D32") (class "Default")
      (node (ref "IC43") (pin "K2") (pinfunction "D32_K2") (pintype "input"))
      (node (ref "RP2") (pin "5") (pinfunction "5_5") (pintype "passive"))
    )
    (net (code "168") (name "/Q2_D33") (class "Default")
      (node (ref "IC43") (pin "M1") (pinfunction "D33_M1") (pintype "input"))
      (node (ref "RP2") (pin "4") (pinfunction "4_4") (pintype "passive"))
    )
    (net (code "169") (name "/Q2_D34") (class "Default")
      (node (ref "IC43") (pin "N1") (pinfunction "D34_N1") (pintype "input"))
      (node (ref "RP2") (pin "3") (pinfunction "3_3") (pintype "passive"))
    )
    (net (code "170") (name "/Q2_D35") (class "Default")
      (node (ref "IC43") (pin "P2") (pinfunction "D35_P2") (pintype "input"))
      (node (ref "RP2") (pin "2") (pinfunction "2_2") (pintype "passive"))
    )
    (net (code "171") (name "/Q2_DOFF") (class "Default")
      (node (ref "IC43") (pin "H1") (pinfunction "~{DOFF}_H1") (pintype "input"))
    )
    (net (code "173") (name "/Q2_K_N") (class "Default")
      (node (ref "IC43") (pin "A6") (pinfunction "~{K}_A6") (pintype "input"))
    )
    (net (code "174") (name "/Q2_K_P") (class "Default")
      (node (ref "IC43") (pin "B6") (pinfunction "K_B6") (pintype "input"))
    )
    (net (code "175") (name "/Q2_Q0") (class "Default")
      (node (ref "IC43") (pin "P11") (pinfunction "Q0_P11") (pintype "output"))
    )
    (net (code "176") (name "/Q2_Q1") (class "Default")
      (node (ref "IC43") (pin "M10") (pinfunction "Q1_M10") (pintype "output"))
    )
    (net (code "177") (name "/Q2_Q2") (class "Default")
      (node (ref "IC43") (pin "L11") (pinfunction "Q2_L11") (pintype "output"))
    )
    (net (code "178") (name "/Q2_Q3") (class "Default")
      (node (ref "IC43") (pin "K11") (pinfunction "Q3_K11") (pintype "output"))
    )
    (net (code "179") (name "/Q2_Q4") (class "Default")
      (node (ref "IC43") (pin "J10") (pinfunction "Q4_J10") (pintype "output"))
    )
    (net (code "180") (name "/Q2_Q5") (class "Default")
      (node (ref "IC43") (pin "F11") (pinfunction "Q5_F11") (pintype "output"))
    )
    (net (code "181") (name "/Q2_Q6") (class "Default")
      (node (ref "IC43") (pin "E11") (pinfunction "Q6_E11") (pintype "output"))
    )
    (net (code "182") (name "/Q2_Q7") (class "Default")
      (node (ref "IC43") (pin "C10") (pinfunction "Q7_C10") (pintype "output"))
    )
    (net (code "183") (name "/Q2_Q8") (class "Default")
      (node (ref "IC43") (pin "B11") (pinfunction "Q8_B11") (pintype "output"))
    )
    (net (code "184") (name "/Q2_Q9") (class "Default")
      (node (ref "IC43") (pin "P9") (pinfunction "Q9_P9") (pintype "output"))
    )
    (net (code "185") (name "/Q2_Q10") (class "Default")
      (node (ref "IC43") (pin "N9") (pinfunction "Q10_N9") (pintype "output"))
    )
    (net (code "186") (name "/Q2_Q11") (class "Default")
      (node (ref "IC43") (pin "L10") (pinfunction "Q11_L10") (pintype "output"))
    )
    (net (code "187") (name "/Q2_Q12") (class "Default")
      (node (ref "IC43") (pin "K9") (pinfunction "Q12_K9") (pintype "output"))
    )
    (net (code "188") (name "/Q2_Q13") (class "Default")
      (node (ref "IC43") (pin "G9") (pinfunction "Q13_G9") (pintype "output"))
    )
    (net (code "189") (name "/Q2_Q14") (class "Default")
      (node (ref "IC43") (pin "F10") (pinfunction "Q14_F10") (pintype "output"))
    )
    (net (code "190") (name "/Q2_Q15") (class "Default")
      (node (ref "IC43") (pin "E9") (pinfunction "Q15_E9") (pintype "output"))
    )
    (net (code "191") (name "/Q2_Q16") (class "Default")
      (node (ref "IC43") (pin "D9") (pinfunction "Q16_D9") (pintype "output"))
    )
    (net (code "192") (name "/Q2_Q17") (class "Default")
      (node (ref "IC43") (pin "B10") (pinfunction "Q17_B10") (pintype "output"))
    )
    (net (code "193") (name "/Q2_Q18") (class "Default")
      (node (ref "IC43") (pin "B2") (pinfunction "Q18_B2") (pintype "output"))
    )
    (net (code "194") (name "/Q2_Q19") (class "Default")
      (node (ref "IC43") (pin "D3") (pinfunction "Q19_D3") (pintype "output"))
    )
    (net (code "195") (name "/Q2_Q20") (class "Default")
      (node (ref "IC43") (pin "E3") (pinfunction "Q20_E3") (pintype "output"))
    )
    (net (code "196") (name "/Q2_Q21") (class "Default")
      (node (ref "IC43") (pin "F2") (pinfunction "Q21_F2") (pintype "output"))
    )
    (net (code "197") (name "/Q2_Q22") (class "Default")
      (node (ref "IC43") (pin "G3") (pinfunction "Q22_G3") (pintype "output"))
    )
    (net (code "198") (name "/Q2_Q23") (class "Default")
      (node (ref "IC43") (pin "K3") (pinfunction "Q23_K3") (pintype "output"))
    )
    (net (code "199") (name "/Q2_Q24") (class "Default")
      (node (ref "IC43") (pin "L2") (pinfunction "Q24_L2") (pintype "output"))
    )
    (net (code "200") (name "/Q2_Q25") (class "Default")
      (node (ref "IC43") (pin "N3") (pinfunction "Q25_N3") (pintype "output"))
    )
    (net (code "201") (name "/Q2_Q26") (class "Default")
      (node (ref "IC43") (pin "P3") (pinfunction "Q26_P3") (pintype "output"))
    )
    (net (code "202") (name "/Q2_Q27") (class "Default")
      (node (ref "IC43") (pin "B1") (pinfunction "Q27_B1") (pintype "output"))
    )
    (net (code "203") (name "/Q2_Q28") (class "Default")
      (node (ref "IC43") (pin "C2") (pinfunction "Q28_C2") (pintype "output"))
    )
    (net (code "204") (name "/Q2_Q29") (class "Default")
      (node (ref "IC43") (pin "E1") (pinfunction "Q29_E1") (pintype "output"))
    )
    (net (code "205") (name "/Q2_Q30") (class "Default")
      (node (ref "IC43") (pin "F1") (pinfunction "Q30_F1") (pintype "output"))
    )
    (net (code "206") (name "/Q2_Q31") (class "Default")
      (node (ref "IC43") (pin "J2") (pinfunction "Q31_J2") (pintype "output"))
    )
    (net (code "207") (name "/Q2_Q32") (class "Default")
      (node (ref "IC43") (pin "K1") (pinfunction "Q32_K1") (pintype "output"))
    )
    (net (code "208") (name "/Q2_Q33") (class "Default")
      (node (ref "IC43") (pin "L1") (pinfunction "Q33_L1") (pintype "output"))
    )
    (net (code "209") (name "/Q2_Q34") (class "Default")
      (node (ref "IC43") (pin "M2") (pinfunction "Q34_M2") (pintype "output"))
    )
    (net (code "210") (name "/Q2_Q35") (class "Default")
      (node (ref "IC43") (pin "P1") (pinfunction "Q35_P1") (pintype "output"))
    )
    (net (code "212") (name "/Q2_RPS") (class "Default")
      (node (ref "IC43") (pin "A8") (pinfunction "~{RPS}_A8") (pintype "input"))
    )
    (net (code "213") (name "/Q2_WPS") (class "Default")
      (node (ref "IC43") (pin "A4") (pinfunction "~{WPS}_A4") (pintype "input"))
    )
    (net (code "219") (name "GND") (class "Default")
      (node (ref "IC42") (pin "R2") (pinfunction "TCK_R2") (pintype "input"))
      (node (ref "IC43") (pin "R2") (pinfunction "TCK_R2") (pintype "input"))
    )
    (net (code "220") (name "QDRII_VTT") (class "Default")
      (node (ref "RP1") (pin "1") (pinfunction "1_1") (pintype "passive"))
      (node (ref "RP1") (pin "6") (pinfunction "6_6") (pintype "passive"))
      (node (ref "RP10") (pin "1") (pinfunction "1_1") (pintype "passive"))
      (node (ref "RP10") (pin "6") (pinfunction "6_6") (pintype "passive"))
      (node (ref "RP11") (pin "1") (pinfunction "1_1") (pintype "passive"))
      (node (ref "RP11") (pin "6") (pinfunction "6_6") (pintype "passive"))
      (node (ref "RP12") (pin "1") (pinfunction "1_1") (pintype "passive"))
      (node (ref "RP12") (pin "6") (pinfunction "6_6") (pintype "passive"))
      (node (ref "RP13") (pin "1") (pinfunction "1_1") (pintype "passive"))
      (node (ref "RP13") (pin "6") (pinfunction "6_6") (pintype "passive"))
      (node (ref "RP14") (pin "1") (pinfunction "1_1") (pintype "passive"))
      (node (ref "RP14") (pin "6") (pinfunction "6_6") (pintype "passive"))
      (node (ref "RP2") (pin "1") (pinfunction "1_1") (pintype "passive"))
      (node (ref "RP2") (pin "6") (pinfunction "6_6") (pintype "passive"))
      (node (ref "RP3") (pin "1") (pinfunction "1_1") (pintype "passive"))
      (node (ref "RP3") (pin "6") (pinfunction "6_6") (pintype "passive"))
      (node (ref "RP4") (pin "1") (pinfunction "1_1") (pintype "passive"))
      (node (ref "RP4") (pin "6") (pinfunction "6_6") (pintype "passive"))
      (node (ref "RP5") (pin "1") (pinfunction "1_1") (pintype "passive"))
      (node (ref "RP5") (pin "6") (pinfunction "6_6") (pintype "passive"))
      (node (ref "RP6") (pin "1") (pinfunction "1_1") (pintype "passive"))
      (node (ref "RP6") (pin "6") (pinfunction "6_6") (pintype "passive"))
      (node (ref "RP7") (pin "1") (pinfunction "1_1") (pintype "passive"))
      (node (ref "RP7") (pin "6") (pinfunction "6_6") (pintype "passive"))
      (node (ref "RP8") (pin "1") (pinfunction "1_1") (pintype "passive"))
      (node (ref "RP8") (pin "6") (pinfunction "6_6") (pintype "passive"))
      (node (ref "RP9") (pin "1") (pinfunction "1_1") (pintype "passive"))
      (node (ref "RP9") (pin "6") (pinfunction "6_6") (pintype "passive"))
    )
    (net (code "221") (name "unconnected-(IC42A-TDI-PadR11)") (class "Default")
      (node (ref "IC42") (pin "R11") (pinfunction "TDI_R11") (pintype "input+no_connect"))
    )
    (net (code "222") (name "unconnected-(IC42A-TDO-PadR1)") (class "Default")
      (node (ref "IC42") (pin "R1") (pinfunction "TDO_R1") (pintype "output"))
    )
    (net (code "223") (name "unconnected-(IC42A-TMS-PadR10)") (class "Default")
      (node (ref "IC42") (pin "R10") (pinfunction "TMS_R10") (pintype "input+no_connect"))
    )
    (net (code "224") (name "unconnected-(IC43A-TDI-PadR11)") (class "Default")
      (node (ref "IC43") (pin "R11") (pinfunction "TDI_R11") (pintype "input+no_connect"))
    )
    (net (code "225") (name "unconnected-(IC43A-TDO-PadR1)") (class "Default")
      (node (ref "IC43") (pin "R1") (pinfunction "TDO_R1") (pintype "output"))
    )
    (net (code "226") (name "unconnected-(IC43A-TMS-PadR10)") (class "Default")
      (node (ref "IC43") (pin "R10") (pinfunction "TMS_R10") (pintype "input+no_connect"))
    )
    (net (code "227") (name "unconnected-(RP1-Pad5)") (class "Default")
      (node (ref "RP1") (pin "5") (pinfunction "5_5") (pintype "passive"))
    )
    (net (code "228") (name "unconnected-(RP2-Pad8)") (class "Default")
      (node (ref "RP2") (pin "8") (pinfunction "8_8") (pintype "passive"))
    )
  )
)
